# V2.net
KiCad netlist of a schematic drawn in Altium Designer
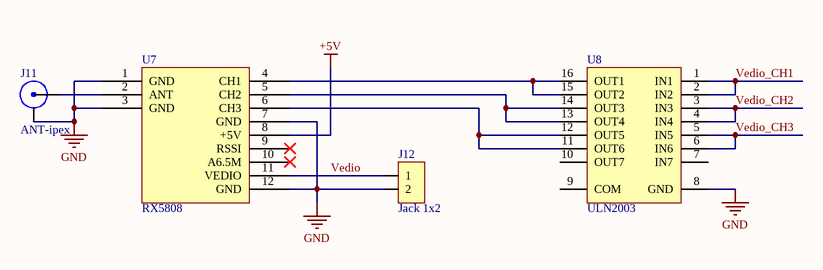
[diagram p0: 海关全向控制器主控板电路V2_图传电路.SchDoc]

(export (version "E")
  (design (tool "Eeschema 10.0.6"))
  (components
    (comp (ref "J11") (value "ANT-ipex") (footprint "IPEX") (libsource (lib "RLCYDF") (part "ANT-ipex")))
    (comp (ref "J12")
      (value "Jack 1x2")
      (footprint "35363-0260")
      (description "插座")
      (libsource (lib "Connector") (part "Jack 1x2"))
    )
    (comp (ref "U7") (value "RX5808") (footprint "RX5808") (libsource (lib "Module") (part "RX5808")))
    (comp (ref "U8") (value "ULN2003") (footprint "SO16") (libsource (lib "Logic Class") (part "ULN2003")))
  )
  (nets
    (net (code "1") (name "+5V") (class "Default")
      (node (ref "U7") (pin "8") (pinfunction "+5V_8") (pintype "passive"))
    )
    (net (code "2") (name "/Vedio") (class "Default")
      (node (ref "J12") (pin "1") (pinfunction "1_1") (pintype "passive"))
      (node (ref "U7") (pin "11") (pinfunction "VEDIO_11") (pintype "passive"))
    )
    (net (code "3") (name "/Vedio_CH1") (class "Default")
      (node (ref "U8") (pin "1") (pinfunction "IN1_1") (pintype "passive"))
      (node (ref "U8") (pin "2") (pinfunction "IN2_2") (pintype "passive"))
    )
    (net (code "4") (name "/Vedio_CH2") (class "Default")
      (node (ref "U8") (pin "3") (pinfunction "IN3_3") (pintype "passive"))
      (node (ref "U8") (pin "4") (pinfunction "IN4_4") (pintype "passive"))
    )
    (net (code "5") (name "/Vedio_CH3") (class "Default")
      (node (ref "U8") (pin "5") (pinfunction "IN5_5") (pintype "passive"))
      (node (ref "U8") (pin "6") (pinfunction "IN6_6") (pintype "passive"))
    )
    (net (code "6") (name "GND") (class "Default")
      (node (ref "J11") (pin "2") (pinfunction "GND_2") (pintype "passive"))
      (node (ref "J12") (pin "2") (pinfunction "2_2") (pintype "passive"))
      (node (ref "U7") (pin "1") (pinfunction "GND_1") (pintype "passive"))
      (node (ref "U7") (pin "12") (pinfunction "GND_12") (pintype "passive"))
      (node (ref "U7") (pin "3") (pinfunction "GND_3") (pintype "passive"))
      (node (ref "U7") (pin "7") (pinfunction "GND_7") (pintype "passive"))
      (node (ref "U8") (pin "8") (pinfunction "GND_8") (pintype "power_in"))
    )
    (net (code "7") (name "Net-(J11-ANT)") (class "Default")
      (node (ref "J11") (pin "1") (pinfunction "ANT_1") (pintype "passive"))
      (node (ref "U7") (pin "2") (pinfunction "ANT_2") (pintype "passive"))
    )
    (net (code "8") (name "Net-(U7-CH1)") (class "Default")
      (node (ref "U7") (pin "4") (pinfunction "CH1_4") (pintype "passive"))
      (node (ref "U8") (pin "15") (pinfunction "OUT2_15") (pintype "open_collector"))
      (node (ref "U8") (pin "16") (pinfunction "OUT1_16") (pintype "open_collector"))
    )
    (net (code "9") (name "Net-(U7-CH2)") (class "Default")
      (node (ref "U7") (pin "5") (pinfunction "CH2_5") (pintype "passive"))
      (node (ref "U8") (pin "13") (pinfunction "OUT4_13") (pintype "open_collector"))
      (node (ref "U8") (pin "14") (pinfunction "OUT3_14") (pintype "open_collector"))
    )
    (net (code "10") (name "Net-(U7-CH3)") (class "Default")
      (node (ref "U7") (pin "6") (pinfunction "CH3_6") (pintype "passive"))
      (node (ref "U8") (pin "11") (pinfunction "OUT6_11") (pintype "open_collector"))
      (node (ref "U8") (pin "12") (pinfunction "OUT5_12") (pintype "open_collector"))
    )
    (net (code "11") (name "unconnected-(U7-A6.5M-Pad10)") (class "Default")
      (node (ref "U7") (pin "10") (pinfunction "A6.5M_10") (pintype "passive+no_connect"))
    )
    (net (code "12") (name "unconnected-(U7-RSSI-Pad9)") (class "Default")
      (node (ref "U7") (pin "9") (pinfunction "RSSI_9") (pintype "passive+no_connect"))
    )
    (net (code "13") (name "unconnected-(U8-COM-Pad9)") (class "Default")
      (node (ref "U8") (pin "9") (pinfunction "COM_9") (pintype "passive"))
    )
    (net (code "14") (name "unconnected-(U8-IN7-Pad7)") (class "Default")
      (node (ref "U8") (pin "7") (pinfunction "IN7_7") (pintype "passive"))
    )
    (net (code "15") (name "unconnected-(U8-OUT7-Pad10)") (class "Default")
      (node (ref "U8") (pin "10") (pinfunction "OUT7_10") (pintype "open_collector"))
    )
  )
)
